# COM_LoRa.net
KiCad netlist of a schematic drawn in Altium Designer
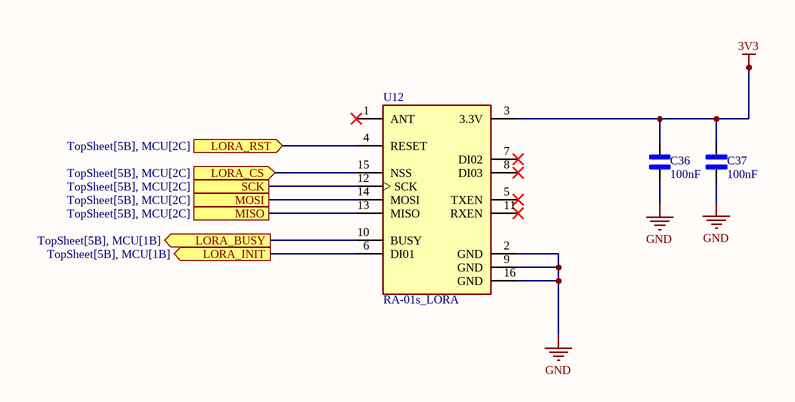
[diagram p0: COM_LoRa.SchDoc]

(export (version "E")
  (design (tool "Eeschema 10.0.6"))
  (components
    (comp (ref "C36")
      (value "100nF")
      (footprint "C0603")
      (fields (field (name "MF") "Murata") (field (name "MP") "GJM1555C1HR10BB01J"))
      (libsource (lib "common component") (part "Capacitor non polar"))
    )
    (comp (ref "C37")
      (value "100nF")
      (footprint "C0603")
      (fields (field (name "MF") "Murata") (field (name "MP") "GJM1555C1HR10BB01J"))
      (libsource (lib "common component") (part "Capacitor non polar"))
    )
    (comp (ref "U12")
      (value "RA-01s_LORA")
      (footprint "MODULE_RA-01s_LORA")
      (description "Ra-02 LoRa RF M5Stack Platform Evaluation Expansion Board")
      (fields (field (name "MP") "RA-02_LORA"))
      (libsource (lib "ra-01s") (part "RA-01s_LORA"))
    )
  )
  (nets
    (net (code "1") (name "/LORA_BUSY") (class "Default")
      (node (ref "U12") (pin "10") (pinfunction "BUSY_10") (pintype "passive"))
    )
    (net (code "2") (name "/LORA_CS") (class "Default")
      (node (ref "U12") (pin "15") (pinfunction "NSS_15") (pintype "passive"))
    )
    (net (code "3") (name "/LORA_INIT") (class "Default")
      (node (ref "U12") (pin "6") (pinfunction "DI01_6") (pintype "passive"))
    )
    (net (code "4") (name "/LORA_RST") (class "Default")
      (node (ref "U12") (pin "4") (pinfunction "RESET_4") (pintype "passive"))
    )
    (net (code "5") (name "/MISO") (class "Default")
      (node (ref "U12") (pin "13") (pinfunction "MISO_13") (pintype "passive"))
    )
    (net (code "6") (name "/MOSI") (class "Default")
      (node (ref "U12") (pin "14") (pinfunction "MOSI_14") (pintype "passive"))
    )
    (net (code "7") (name "/SCK") (class "Default")
      (node (ref "U12") (pin "12") (pinfunction "SCK_12") (pintype "passive"))
    )
    (net (code "8") (name "3V3") (class "Default")
      (node (ref "C36") (pin "2") (pinfunction "2_2") (pintype "passive"))
      (node (ref "C37") (pin "2") (pinfunction "2_2") (pintype "passive"))
      (node (ref "U12") (pin "3") (pinfunction "3.3V_3") (pintype "power_in"))
    )
    (net (code "9") (name "GND") (class "Default")
      (node (ref "C36") (pin "1") (pinfunction "1_1") (pintype "passive"))
      (node (ref "C37") (pin "1") (pinfunction "1_1") (pintype "passive"))
      (node (ref "U12") (pin "16") (pinfunction "GND_16") (pintype "power_in"))
      (node (ref "U12") (pin "2") (pinfunction "GND_2") (pintype "power_in"))
      (node (ref "U12") (pin "9") (pinfunction "GND_9") (pintype "power_in"))
    )
    (net (code "10") (name "unconnected-(U12-ANT-Pad1)") (class "Default")
      (node (ref "U12") (pin "1") (pinfunction "ANT_1") (pintype "power_in+no_connect"))
    )
    (net (code "11") (name "unconnected-(U12-DI02-Pad7)") (class "Default")
      (node (ref "U12") (pin "7") (pinfunction "DI02_7") (pintype "passive+no_connect"))
    )
    (net (code "12") (name "unconnected-(U12-DI03-Pad8)") (class "Default")
      (node (ref "U12") (pin "8") (pinfunction "DI03_8") (pintype "passive+no_connect"))
    )
    (net (code "13") (name "unconnected-(U12-RXEN-Pad11)") (class "Default")
      (node (ref "U12") (pin "11") (pinfunction "RXEN_11") (pintype "passive+no_connect"))
    )
    (net (code "14") (name "unconnected-(U12-TXEN-Pad5)") (class "Default")
      (node (ref "U12") (pin "5") (pinfunction "TXEN_5") (pintype "passive+no_connect"))
    )
  )
)
